# misc.net
KiCad netlist of a schematic drawn in Altium Designer
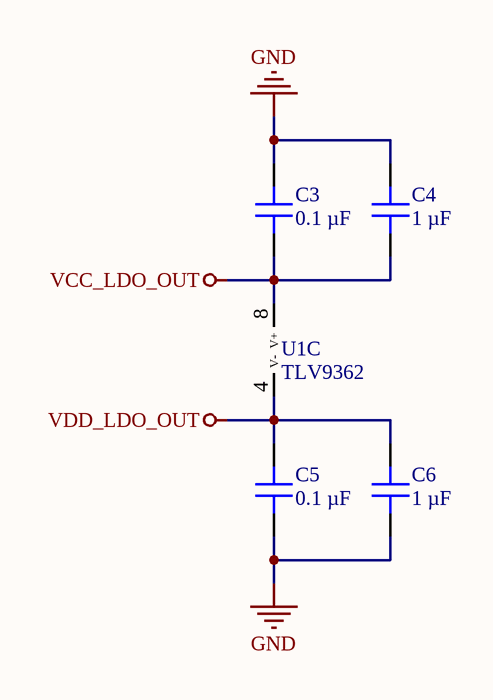
[diagram p0: misc.SchDoc]

(export (version "E")
  (design (tool "Eeschema 10.0.6"))
  (components
    (comp (ref "C3")
      (value "0.1 µF")
      (footprint "CAP 1206_3216 - 0.8MM")
      (description "CAP CER 0.1UF 50V X7R 1206")
      (fields
        (field (name "PART NUMBER") "885012208087")
        (field (name "CAPACITANCE") "0.1 µF")
        (field (name "MANUFACTURER") "Würth Elektronik")
      )
      (libsource (lib "Celestial Altium Library - altium_library") (part "Capacitor"))
    )
    (comp (ref "C4")
      (value "1 µF")
      (footprint "CAP 1206_3216 - 0.8MM")
      (description "CAP CER 1UF 50V X7R 1206")
      (fields
        (field (name "PART NUMBER") "885012208093")
        (field (name "CAPACITANCE") "1 µF")
        (field (name "MANUFACTURER") "Würth Elektronik")
      )
      (libsource (lib "Celestial Altium Library - altium_library") (part "Capacitor"))
    )
    (comp (ref "C5")
      (value "0.1 µF")
      (footprint "CAP 1206_3216 - 0.8MM")
      (description "CAP CER 0.1UF 50V X7R 1206")
      (fields
        (field (name "PART NUMBER") "885012208087")
        (field (name "CAPACITANCE") "0.1 µF")
        (field (name "MANUFACTURER") "Würth Elektronik")
      )
      (libsource (lib "Celestial Altium Library - altium_library") (part "Capacitor"))
    )
    (comp (ref "C6")
      (value "1 µF")
      (footprint "CAP 1206_3216 - 0.8MM")
      (description "CAP CER 1UF 50V X7R 1206")
      (fields
        (field (name "PART NUMBER") "885012208093")
        (field (name "CAPACITANCE") "1 µF")
        (field (name "MANUFACTURER") "Würth Elektronik")
      )
      (libsource (lib "Celestial Altium Library - altium_library") (part "Capacitor"))
    )
    (comp (ref "U1")
      (value "TLV9362")
      (footprint "SOIC8-127P600X175-8N")
      (description "TLV936x 10-MHz, 40-V, RRO, Operational Amplifie")
      (libsource (lib "za_koncar") (part "TLV9362"))
    )
  )
  (nets
    (net (code "1") (name "GND") (class "Default")
      (node (ref "C3") (pin "2") (pinfunction "2_2") (pintype "passive"))
      (node (ref "C4") (pin "2") (pinfunction "2_2") (pintype "passive"))
      (node (ref "C5") (pin "2") (pinfunction "2_2") (pintype "passive"))
      (node (ref "C6") (pin "2") (pinfunction "2_2") (pintype "passive"))
    )
    (net (code "2") (name "VCC_LDO_OUT") (class "Default")
      (node (ref "C3") (pin "1") (pinfunction "1_1") (pintype "passive"))
      (node (ref "C4") (pin "1") (pinfunction "1_1") (pintype "passive"))
      (node (ref "U1") (pin "8") (pinfunction "V+_8") (pintype "power_in"))
    )
    (net (code "3") (name "VDD_LDO_OUT") (class "Default")
      (node (ref "C5") (pin "1") (pinfunction "1_1") (pintype "passive"))
      (node (ref "C6") (pin "1") (pinfunction "1_1") (pintype "passive"))
      (node (ref "U1") (pin "4") (pinfunction "V-_4") (pintype "power_in"))
    )
  )
)
